# MicroSD_Card.net
KiCad netlist of a schematic drawn in Altium Designer
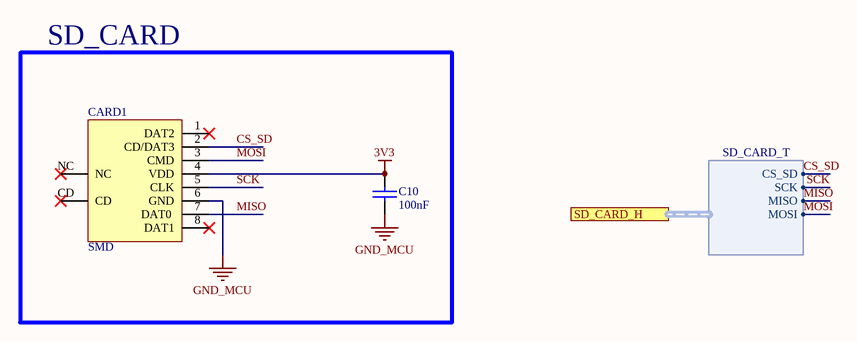
[diagram p0: MicroSD_Card.SchDoc]

(export (version "E")
  (design (tool "Eeschema 10.0.6"))
  (components
    (comp (ref "C10")
      (value "100nF")
      (footprint "0603_cap")
      (description "50V 100nF X7R ±10% 0603 Ceramic Capacitors RoHS")
      (fields
        (field (name "MANUFACTURER") "FOJAN")
        (field (name "MANUFACTURER PART NUMBER") "FCC0603B104K500CT")
      )
      (libsource (lib "CNCLib") (part "Cap_100nF_0603_50V"))
    )
    (comp (ref "CARD1")
      (value "SMD")
      (footprint "SD_CARD_PUSH_PCB")
      (description "Push-Push 2mm Connector and Ejector MicroSD Card (TF Card) SMD PC Card Sockets RoHS")
      (fields (field (name "MANUFACTURER") "Yuandi") (field (name "MANUFACTURER PART NUMBER") "TF-01A"))
      (libsource (lib "CNCLib") (part "SD_CARD_PUSH"))
    )
  )
  (nets
    (net (code "2") (name "/CS_SD") (class "Default")
      (node (ref "CARD1") (pin "2") (pinfunction "CD/DAT3_2") (pintype "passive"))
    )
    (net (code "3") (name "/MISO") (class "Default")
      (node (ref "CARD1") (pin "7") (pinfunction "DAT0_7") (pintype "passive"))
    )
    (net (code "4") (name "/MOSI") (class "Default")
      (node (ref "CARD1") (pin "3") (pinfunction "CMD_3") (pintype "passive"))
    )
    (net (code "5") (name "/SCK") (class "Default")
      (node (ref "CARD1") (pin "5") (pinfunction "CLK_5") (pintype "passive"))
    )
    (net (code "7") (name "3V3") (class "Default")
      (node (ref "C10") (pin "1") (pinfunction "1_1") (pintype "passive"))
      (node (ref "CARD1") (pin "4") (pinfunction "VDD_4") (pintype "passive"))
    )
    (net (code "8") (name "GND_MCU") (class "Default")
      (node (ref "C10") (pin "2") (pinfunction "2_2") (pintype "passive"))
      (node (ref "CARD1") (pin "6") (pinfunction "GND_6") (pintype "passive"))
    )
    (net (code "9") (name "unconnected-(CARD1-DAT1-Pad8)") (class "Default")
      (node (ref "CARD1") (pin "8") (pinfunction "DAT1_8") (pintype "passive+no_connect"))
    )
    (net (code "10") (name "unconnected-(CARD1-DAT2-Pad1)") (class "Default")
      (node (ref "CARD1") (pin "1") (pinfunction "DAT2_1") (pintype "passive+no_connect"))
    )
    (net (code "11") (name "unconnected-(CARD1-PadCD)") (class "Default")
      (node (ref "CARD1") (pin "CD") (pinfunction "CD_CD") (pintype "passive+no_connect"))
    )
    (net (code "12") (name "unconnected-(CARD1-PadNC)") (class "Default")
      (node (ref "CARD1") (pin "NC") (pinfunction "NC_NC") (pintype "passive+no_connect"))
    )
  )
)
